# Connectors.net
KiCad netlist of a schematic drawn in Altium Designer
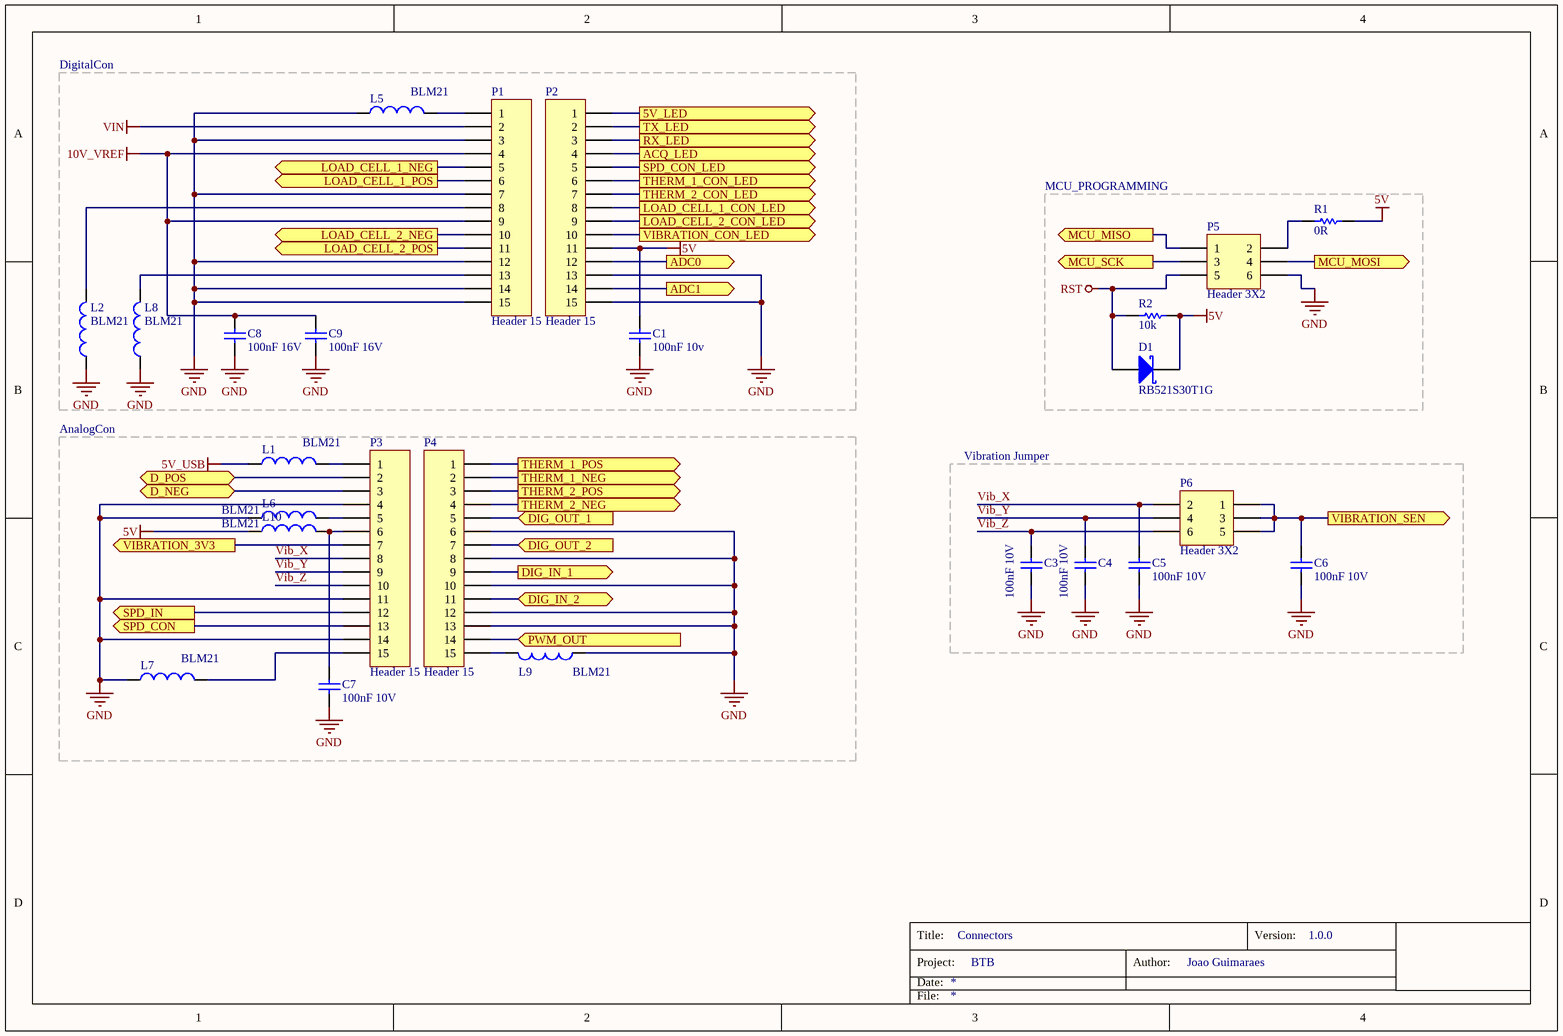
[diagram p0: Connectors.SchDoc]

(export (version "E")
  (design (tool "Eeschema 10.0.6"))
  (components
    (comp (ref "C1")
      (value "100nF 10v")
      (footprint "C0805")
      (description "Capacitor")
      (fields (field (name "PARTNUMBER") "CAP.100n.10V.20%.SMD.0402") (field (name "MANUFACTURER") "Wurth"))
      (libsource (lib "IntLib") (part "Cap"))
    )
    (comp (ref "C3")
      (value "100nF 10V")
      (footprint "C0805")
      (description "Capacitor")
      (fields (field (name "PARTNUMBER") "CAP.100n.10V.20%.SMD.0402") (field (name "MANUFACTURER") "Wurth"))
      (libsource (lib "IntLib") (part "Cap"))
    )
    (comp (ref "C4")
      (value "100nF 10V")
      (footprint "C0805")
      (description "Capacitor")
      (fields (field (name "PARTNUMBER") "CAP.100n.10V.20%.SMD.0402") (field (name "MANUFACTURER") "Wurth"))
      (libsource (lib "IntLib") (part "Cap"))
    )
    (comp (ref "C5")
      (value "100nF 10V")
      (footprint "C0805")
      (description "Capacitor")
      (fields (field (name "PARTNUMBER") "CAP.100n.10V.20%.SMD.0402") (field (name "MANUFACTURER") "Wurth"))
      (libsource (lib "IntLib") (part "Cap"))
    )
    (comp (ref "C6")
      (value "100nF 10V")
      (footprint "C0805")
      (description "Capacitor")
      (fields (field (name "PARTNUMBER") "CAP.100n.10V.20%.SMD.0402") (field (name "MANUFACTURER") "Wurth"))
      (libsource (lib "IntLib") (part "Cap"))
    )
    (comp (ref "C7")
      (value "100nF 10V")
      (footprint "C0805")
      (description "Capacitor")
      (fields (field (name "PARTNUMBER") "CAP.100n.10V.20%.SMD.0402") (field (name "MANUFACTURER") "Wurth"))
      (libsource (lib "IntLib") (part "Cap"))
    )
    (comp (ref "C8")
      (value "100nF 16V")
      (footprint "C0805")
      (description "Capacitor")
      (fields (field (name "PARTNUMBER") "CAP.100n.10V.20%.SMD.0402") (field (name "MANUFACTURER") "Wurth"))
      (libsource (lib "IntLib") (part "Cap"))
    )
    (comp (ref "C9")
      (value "100nF 16V")
      (footprint "C0805")
      (description "Capacitor")
      (fields (field (name "PARTNUMBER") "CAP.100n.10V.20%.SMD.0402") (field (name "MANUFACTURER") "Wurth"))
      (libsource (lib "IntLib") (part "Cap"))
    )
    (comp (ref "D1")
      (value "RB521S30T1G")
      (footprint "SOD-523")
      (description "Schottky Diodes & Rectifiers 30V 200mW Single")
      (fields (field (name "MANUFACTURER") "ON Semiconductor"))
      (libsource (lib "IntLib") (part "RB521S30T1G"))
    )
    (comp (ref "L1")
      (value "BLM21")
      (footprint "6-0805_M")
      (description "Chip Inductor")
      (fields (field (name "MANUFACTURER") "Murata Electronics"))
      (libsource (lib "IntLib") (part "Inductor"))
    )
    (comp (ref "L2")
      (value "BLM21")
      (footprint "6-0805_M")
      (description "Chip Inductor")
      (fields (field (name "MANUFACTURER") "Murata Electronics"))
      (libsource (lib "IntLib") (part "Inductor"))
    )
    (comp (ref "L5")
      (value "BLM21")
      (footprint "6-0805_M")
      (description "Chip Inductor")
      (fields (field (name "MANUFACTURER") "Murata Electronics"))
      (libsource (lib "IntLib") (part "Inductor"))
    )
    (comp (ref "L6")
      (value "BLM21")
      (footprint "6-0805_M")
      (description "Chip Inductor")
      (fields (field (name "MANUFACTURER") "Murata Electronics"))
      (libsource (lib "IntLib") (part "Inductor"))
    )
    (comp (ref "L7")
      (value "BLM21")
      (footprint "6-0805_M")
      (description "Chip Inductor")
      (fields (field (name "MANUFACTURER") "Murata Electronics"))
      (libsource (lib "IntLib") (part "Inductor"))
    )
    (comp (ref "L8")
      (value "BLM21")
      (footprint "6-0805_M")
      (description "Chip Inductor")
      (fields (field (name "MANUFACTURER") "Murata Electronics"))
      (libsource (lib "IntLib") (part "Inductor"))
    )
    (comp (ref "L9")
      (value "BLM21")
      (footprint "6-0805_M")
      (description "Chip Inductor")
      (fields (field (name "MANUFACTURER") "Murata Electronics"))
      (libsource (lib "IntLib") (part "Inductor"))
    )
    (comp (ref "L10")
      (value "BLM21")
      (footprint "6-0805_M")
      (description "Chip Inductor")
      (fields (field (name "MANUFACTURER") "Murata Electronics"))
      (libsource (lib "IntLib") (part "Inductor"))
    )
    (comp (ref "P1")
      (value "Header 15")
      (footprint "HDR1X15")
      (description "Header, 15-Pin")
      (libsource (lib "") (part "Header 15_1"))
    )
    (comp (ref "P2")
      (value "Header 15")
      (footprint "HDR1X15")
      (description "Header, 15-Pin")
      (libsource (lib "IntLib") (part "Header 15"))
    )
    (comp (ref "P3")
      (value "Header 15")
      (footprint "HDR1X15")
      (description "Header, 15-Pin")
      (libsource (lib "") (part "Header 15_1"))
    )
    (comp (ref "P4")
      (value "Header 15")
      (footprint "HDR1X15")
      (description "Header, 15-Pin")
      (libsource (lib "IntLib") (part "Header 15"))
    )
    (comp (ref "P5")
      (value "Header 3X2")
      (footprint "HDR2X3")
      (description "Header, 3-Pin, Dual row")
      (libsource (lib "") (part "Header 3X2_1"))
    )
    (comp (ref "P6")
      (value "Header 3X2")
      (footprint "HDR2X3")
      (description "Header, 3-Pin, Dual row")
      (libsource (lib "IntLib") (part "Header 3X2"))
    )
    (comp (ref "R1")
      (value "0R")
      (footprint "6-0805_M")
      (description "Resistor")
      (fields (field (name "PARTNUMBER") "RES.0R.1/8W.5%.SMD.0805") (field (name "MANUFACTURER") "Vishay"))
      (libsource (lib "IntLib") (part "Res"))
    )
    (comp (ref "R2")
      (value "10k")
      (footprint "6-0805_M")
      (description "Resistor")
      (fields (field (name "PARTNUMBER") "RES.10K.1/8W.5%.SMD.0805") (field (name "MANUFACTURER") "Yageo"))
      (libsource (lib "IntLib") (part "Res"))
    )
  )
  (nets
    (net (code "1") (name "/5V_LED") (class "Default")
      (node (ref "P2") (pin "1") (pinfunction "1_1") (pintype "passive"))
    )
    (net (code "2") (name "/ACQ_LED") (class "Default")
      (node (ref "P2") (pin "4") (pinfunction "4_4") (pintype "passive"))
    )
    (net (code "3") (name "/ADC0") (class "Default")
      (node (ref "P2") (pin "12") (pinfunction "12_12") (pintype "passive"))
    )
    (net (code "4") (name "/ADC1") (class "Default")
      (node (ref "P2") (pin "14") (pinfunction "14_14") (pintype "passive"))
    )
    (net (code "5") (name "/DIG_IN_1") (class "Default")
      (node (ref "P4") (pin "9") (pinfunction "9_9") (pintype "passive"))
    )
    (net (code "6") (name "/DIG_IN_2") (class "Default")
      (node (ref "P4") (pin "11") (pinfunction "11_11") (pintype "passive"))
    )
    (net (code "7") (name "/DIG_OUT_1") (class "Default")
      (node (ref "P4") (pin "5") (pinfunction "5_5") (pintype "passive"))
    )
    (net (code "8") (name "/DIG_OUT_2") (class "Default")
      (node (ref "P4") (pin "7") (pinfunction "7_7") (pintype "passive"))
    )
    (net (code "9") (name "/D_NEG") (class "Default")
      (node (ref "P3") (pin "3") (pinfunction "3_3") (pintype "passive"))
    )
    (net (code "10") (name "/D_POS") (class "Default")
      (node (ref "P3") (pin "2") (pinfunction "2_2") (pintype "passive"))
    )
    (net (code "11") (name "/LOAD_CELL_1_CON_LED") (class "Default")
      (node (ref "P2") (pin "8") (pinfunction "8_8") (pintype "passive"))
    )
    (net (code "12") (name "/LOAD_CELL_1_NEG") (class "Default")
      (node (ref "P1") (pin "5") (pinfunction "5_5") (pintype "passive"))
    )
    (net (code "13") (name "/LOAD_CELL_1_POS") (class "Default")
      (node (ref "P1") (pin "6") (pinfunction "6_6") (pintype "passive"))
    )
    (net (code "14") (name "/LOAD_CELL_2_CON_LED") (class "Default")
      (node (ref "P2") (pin "9") (pinfunction "9_9") (pintype "passive"))
    )
    (net (code "15") (name "/LOAD_CELL_2_NEG") (class "Default")
      (node (ref "P1") (pin "10") (pinfunction "10_10") (pintype "passive"))
    )
    (net (code "16") (name "/LOAD_CELL_2_POS") (class "Default")
      (node (ref "P1") (pin "11") (pinfunction "11_11") (pintype "passive"))
    )
    (net (code "17") (name "/MCU_MISO") (class "Default")
      (node (ref "P5") (pin "1") (pinfunction "1_1") (pintype "passive"))
    )
    (net (code "18") (name "/MCU_MOSI") (class "Default")
      (node (ref "P5") (pin "4") (pinfunction "4_4") (pintype "passive"))
    )
    (net (code "19") (name "/MCU_SCK") (class "Default")
      (node (ref "P5") (pin "3") (pinfunction "3_3") (pintype "passive"))
    )
    (net (code "20") (name "/PWM_OUT") (class "Default")
      (node (ref "P4") (pin "14") (pinfunction "14_14") (pintype "passive"))
    )
    (net (code "21") (name "/RX_LED") (class "Default")
      (node (ref "P2") (pin "3") (pinfunction "3_3") (pintype "passive"))
    )
    (net (code "22") (name "/SPD_CON") (class "Default")
      (node (ref "P3") (pin "13") (pinfunction "13_13") (pintype "passive"))
    )
    (net (code "23") (name "/SPD_CON_LED") (class "Default")
      (node (ref "P2") (pin "5") (pinfunction "5_5") (pintype "passive"))
    )
    (net (code "24") (name "/SPD_IN") (class "Default")
      (node (ref "P3") (pin "12") (pinfunction "12_12") (pintype "passive"))
    )
    (net (code "25") (name "/THERM_1_CON_LED") (class "Default")
      (node (ref "P2") (pin "6") (pinfunction "6_6") (pintype "passive"))
    )
    (net (code "26") (name "/THERM_1_NEG") (class "Default")
      (node (ref "P4") (pin "2") (pinfunction "2_2") (pintype "passive"))
    )
    (net (code "27") (name "/THERM_1_POS") (class "Default")
      (node (ref "P4") (pin "1") (pinfunction "1_1") (pintype "passive"))
    )
    (net (code "28") (name "/THERM_2_CON_LED") (class "Default")
      (node (ref "P2") (pin "7") (pinfunction "7_7") (pintype "passive"))
    )
    (net (code "29") (name "/THERM_2_NEG") (class "Default")
      (node (ref "P4") (pin "4") (pinfunction "4_4") (pintype "passive"))
    )
    (net (code "30") (name "/THERM_2_POS") (class "Default")
      (node (ref "P4") (pin "3") (pinfunction "3_3") (pintype "passive"))
    )
    (net (code "31") (name "/TX_LED") (class "Default")
      (node (ref "P2") (pin "2") (pinfunction "2_2") (pintype "passive"))
    )
    (net (code "32") (name "/VIBRATION_3V3") (class "Default")
      (node (ref "P3") (pin "7") (pinfunction "7_7") (pintype "passive"))
    )
    (net (code "33") (name "/VIBRATION_CON_LED") (class "Default")
      (node (ref "P2") (pin "10") (pinfunction "10_10") (pintype "passive"))
    )
    (net (code "34") (name "/VIBRATION_SEN") (class "Default")
      (node (ref "C6") (pin "2") (pinfunction "2_2") (pintype "passive"))
      (node (ref "P6") (pin "1") (pinfunction "1_1") (pintype "passive"))
      (node (ref "P6") (pin "3") (pinfunction "3_3") (pintype "passive"))
      (node (ref "P6") (pin "5") (pinfunction "5_5") (pintype "passive"))
    )
    (net (code "35") (name "/Vib_X") (class "Default")
      (node (ref "C5") (pin "2") (pinfunction "2_2") (pintype "passive"))
      (node (ref "P3") (pin "8") (pinfunction "8_8") (pintype "passive"))
      (node (ref "P6") (pin "2") (pinfunction "2_2") (pintype "passive"))
    )
    (net (code "36") (name "/Vib_Y") (class "Default")
      (node (ref "C4") (pin "2") (pinfunction "2_2") (pintype "passive"))
      (node (ref "P3") (pin "9") (pinfunction "9_9") (pintype "passive"))
      (node (ref "P6") (pin "4") (pinfunction "4_4") (pintype "passive"))
    )
    (net (code "37") (name "/Vib_Z") (class "Default")
      (node (ref "C3") (pin "2") (pinfunction "2_2") (pintype "passive"))
      (node (ref "P3") (pin "10") (pinfunction "10_10") (pintype "passive"))
      (node (ref "P6") (pin "6") (pinfunction "6_6") (pintype "passive"))
    )
    (net (code "38") (name "5V") (class "Default")
      (node (ref "C1") (pin "2") (pinfunction "2_2") (pintype "passive"))
      (node (ref "D1") (pin "2") (pinfunction "K_2") (pintype "passive"))
      (node (ref "L10") (pin "1") (pinfunction "1_1") (pintype "passive"))
      (node (ref "P2") (pin "11") (pinfunction "11_11") (pintype "passive"))
      (node (ref "R1") (pin "2") (pinfunction "2_2") (pintype "passive"))
      (node (ref "R2") (pin "2") (pinfunction "2_2") (pintype "passive"))
    )
    (net (code "39") (name "5V_USB") (class "Default")
      (node (ref "L1") (pin "1") (pinfunction "1_1") (pintype "passive"))
    )
    (net (code "40") (name "10V_VREF") (class "Default")
      (node (ref "C8") (pin "2") (pinfunction "2_2") (pintype "passive"))
      (node (ref "C9") (pin "2") (pinfunction "2_2") (pintype "passive"))
      (node (ref "P1") (pin "4") (pinfunction "4_4") (pintype "passive"))
      (node (ref "P1") (pin "9") (pinfunction "9_9") (pintype "passive"))
    )
    (net (code "41") (name "GND") (class "Default")
      (node (ref "C1") (pin "1") (pinfunction "1_1") (pintype "passive"))
      (node (ref "C3") (pin "1") (pinfunction "1_1") (pintype "passive"))
      (node (ref "C4") (pin "1") (pinfunction "1_1") (pintype "passive"))
      (node (ref "C5") (pin "1") (pinfunction "1_1") (pintype "passive"))
      (node (ref "C6") (pin "1") (pinfunction "1_1") (pintype "passive"))
      (node (ref "C7") (pin "1") (pinfunction "1_1") (pintype "passive"))
      (node (ref "C8") (pin "1") (pinfunction "1_1") (pintype "passive"))
      (node (ref "C9") (pin "1") (pinfunction "1_1") (pintype "passive"))
      (node (ref "L2") (pin "1") (pinfunction "1_1") (pintype "passive"))
      (node (ref "L5") (pin "1") (pinfunction "1_1") (pintype "passive"))
      (node (ref "L6") (pin "1") (pinfunction "1_1") (pintype "passive"))
      (node (ref "L7") (pin "1") (pinfunction "1_1") (pintype "passive"))
      (node (ref "L8") (pin "1") (pinfunction "1_1") (pintype "passive"))
      (node (ref "L9") (pin "1") (pinfunction "1_1") (pintype "passive"))
      (node (ref "P1") (pin "12") (pinfunction "12_12") (pintype "passive"))
      (node (ref "P1") (pin "14") (pinfunction "14_14") (pintype "passive"))
      (node (ref "P1") (pin "15") (pinfunction "15_15") (pintype "passive"))
      (node (ref "P1") (pin "3") (pinfunction "3_3") (pintype "passive"))
      (node (ref "P1") (pin "7") (pinfunction "7_7") (pintype "passive"))
      (node (ref "P2") (pin "13") (pinfunction "13_13") (pintype "passive"))
      (node (ref "P2") (pin "15") (pinfunction "15_15") (pintype "passive"))
      (node (ref "P3") (pin "11") (pinfunction "11_11") (pintype "passive"))
      (node (ref "P3") (pin "14") (pinfunction "14_14") (pintype "passive"))
      (node (ref "P3") (pin "4") (pinfunction "4_4") (pintype "passive"))
      (node (ref "P4") (pin "10") (pinfunction "10_10") (pintype "passive"))
      (node (ref "P4") (pin "12") (pinfunction "12_12") (pintype "passive"))
      (node (ref "P4") (pin "13") (pinfunction "13_13") (pintype "passive"))
      (node (ref "P4") (pin "6") (pinfunction "6_6") (pintype "passive"))
      (node (ref "P4") (pin "8") (pinfunction "8_8") (pintype "passive"))
      (node (ref "P5") (pin "6") (pinfunction "6_6") (pintype "passive"))
    )
    (net (code "42") (name "Net-(C7-Pad2)") (class "Default")
      (node (ref "C7") (pin "2") (pinfunction "2_2") (pintype "passive"))
      (node (ref "L10") (pin "2") (pinfunction "2_2") (pintype "passive"))
      (node (ref "P3") (pin "6") (pinfunction "6_6") (pintype "passive"))
    )
    (net (code "43") (name "Net-(L1-Pad2)") (class "Default")
      (node (ref "L1") (pin "2") (pinfunction "2_2") (pintype "passive"))
      (node (ref "P3") (pin "1") (pinfunction "1_1") (pintype "passive"))
    )
    (net (code "44") (name "Net-(L2-Pad2)") (class "Default")
      (node (ref "L2") (pin "2") (pinfunction "2_2") (pintype "passive"))
      (node (ref "P1") (pin "8") (pinfunction "8_8") (pintype "passive"))
    )
    (net (code "45") (name "Net-(L5-Pad2)") (class "Default")
      (node (ref "L5") (pin "2") (pinfunction "2_2") (pintype "passive"))
      (node (ref "P1") (pin "1") (pinfunction "1_1") (pintype "passive"))
    )
    (net (code "46") (name "Net-(L6-Pad2)") (class "Default")
      (node (ref "L6") (pin "2") (pinfunction "2_2") (pintype "passive"))
      (node (ref "P3") (pin "5") (pinfunction "5_5") (pintype "passive"))
    )
    (net (code "47") (name "Net-(L7-Pad2)") (class "Default")
      (node (ref "L7") (pin "2") (pinfunction "2_2") (pintype "passive"))
      (node (ref "P3") (pin "15") (pinfunction "15_15") (pintype "passive"))
    )
    (net (code "48") (name "Net-(L8-Pad2)") (class "Default")
      (node (ref "L8") (pin "2") (pinfunction "2_2") (pintype "passive"))
      (node (ref "P1") (pin "13") (pinfunction "13_13") (pintype "passive"))
    )
    (net (code "49") (name "Net-(L9-Pad2)") (class "Default")
      (node (ref "L9") (pin "2") (pinfunction "2_2") (pintype "passive"))
      (node (ref "P4") (pin "15") (pinfunction "15_15") (pintype "passive"))
    )
    (net (code "50") (name "Net-(P5-Pad2)") (class "Default")
      (node (ref "P5") (pin "2") (pinfunction "2_2") (pintype "passive"))
      (node (ref "R1") (pin "1") (pinfunction "1_1") (pintype "passive"))
    )
    (net (code "51") (name "RST") (class "Default")
      (node (ref "D1") (pin "1") (pinfunction "A_1") (pintype "passive"))
      (node (ref "P5") (pin "5") (pinfunction "5_5") (pintype "passive"))
      (node (ref "R2") (pin "1") (pinfunction "1_1") (pintype "passive"))
    )
    (net (code "52") (name "VIN") (class "Default")
      (node (ref "P1") (pin "2") (pinfunction "2_2") (pintype "passive"))
    )
  )
)
